# TopDrivers.net
KiCad netlist of a schematic drawn in Altium Designer
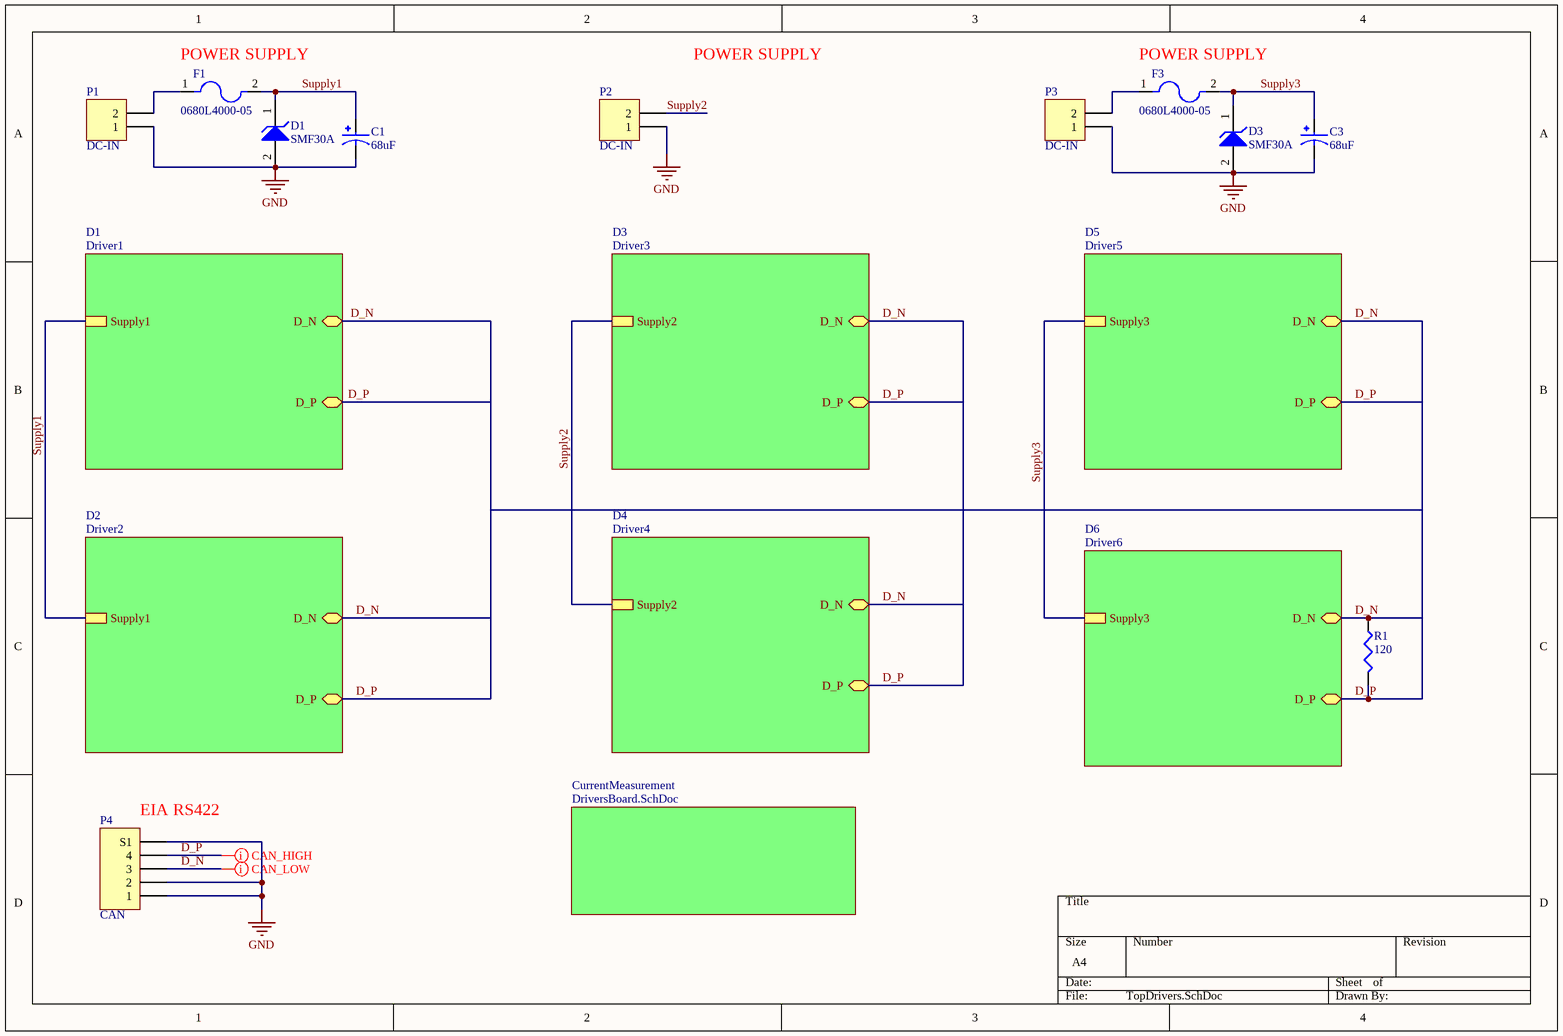
[diagram p0: TopDrivers.SchDoc]

(export (version "E")
  (design (tool "Eeschema 10.0.6"))
  (components
    (comp (ref "C1")
      (value "68uF")
      (footprint "CAP_50SVT68M")
      (fields (field (name "MP") "50SVT68M"))
      (libsource (lib "DriverLib") (part "50SVT68M"))
    )
    (comp (ref "C3")
      (value "68uF")
      (footprint "CAP_50SVT68M")
      (fields (field (name "MP") "50SVT68M"))
      (libsource (lib "DriverLib") (part "50SVT68M"))
    )
    (comp (ref "D1")
      (value "SMF30A")
      (footprint "ONSC-SOD-123FL-2-498_V")
      (description "200 W Transient Voltage Suppressor, 2-Pin SOD-123FL, Pb-Free, Tape and Reel")
      (fields (field (name "MANUFACTURER") "On Semiconductor") (field (name "PARTNUMBER") "SMF30AT1G"))
      (libsource (lib "SpaceBee") (part "SMF30AT1G"))
    )
    (comp (ref "D3")
      (value "SMF30A")
      (footprint "ONSC-SOD-123FL-2-498_V")
      (description "200 W Transient Voltage Suppressor, 2-Pin SOD-123FL, Pb-Free, Tape and Reel")
      (fields (field (name "MANUFACTURER") "On Semiconductor") (field (name "PARTNUMBER") "SMF30AT1G"))
      (libsource (lib "SpaceBee") (part "SMF30AT1G"))
    )
    (comp (ref "F1")
      (value "0680L4000-05")
      (footprint "FUSC6125X279N")
      (description "Surface mount bricks ¦ Silver Plated ¦ 2410 case size ¦ Slow Blow ¦ 4A ¦ Tape and Reel (5000 pcs.)")
      (fields (field (name "MF") "Bel Fuse"))
      (libsource (lib "DriverLib") (part "0680L4000-05"))
    )
    (comp (ref "F3")
      (value "0680L4000-05")
      (footprint "FUSC6125X279N")
      (description "Surface mount bricks ¦ Silver Plated ¦ 2410 case size ¦ Slow Blow ¦ 4A ¦ Tape and Reel (5000 pcs.)")
      (fields (field (name "MF") "Bel Fuse"))
      (libsource (lib "DriverLib") (part "0680L4000-05"))
    )
    (comp (ref "P1")
      (value "DC-IN")
      (footprint "MOLEX_1724480002")
      (description "Header, 2-Pin")
      (fields (field (name "PUBLISHER") "Altium Limited"))
      (libsource (lib "SpaceBee") (part "Header 2"))
    )
    (comp (ref "P2")
      (value "DC-IN")
      (footprint "MOLEX_1724480002")
      (description "Header, 2-Pin")
      (fields (field (name "PUBLISHER") "Altium Limited"))
      (libsource (lib "SpaceBee") (part "Header 2"))
    )
    (comp (ref "P3")
      (value "DC-IN")
      (footprint "MOLEX_1724480002")
      (description "Header, 2-Pin")
      (fields (field (name "PUBLISHER") "Altium Limited"))
      (libsource (lib "SpaceBee") (part "Header 2"))
    )
    (comp (ref "P4")
      (value "CAN")
      (footprint "MOLEX_5025850470")
      (description "Header, 5-Pin")
      (fields (field (name "PUBLISHER") "Altium Limited"))
      (libsource (lib "SpaceBee") (part "Header 5"))
    )
    (comp (ref "R1")
      (value "120")
      (footprint "J1-0603")
      (description "Resistor")
      (fields (field (name "Comment") "Res3") (field (name "PUBLISHER") "Altium Limited"))
      (libsource (lib "Miscellaneous Devices") (part "Res3"))
    )
  )
  (nets
    (net (code "1") (name "/D_N") (class "Default")
      (node (ref "P4") (pin "3") (pinfunction "3_3") (pintype "passive"))
      (node (ref "R1") (pin "1") (pinfunction "1_1") (pintype "passive"))
    )
    (net (code "2") (name "/D_P") (class "Default")
      (node (ref "P4") (pin "4") (pinfunction "4_4") (pintype "passive"))
      (node (ref "R1") (pin "2") (pinfunction "2_2") (pintype "passive"))
    )
    (net (code "3") (name "/Supply1") (class "Default")
      (node (ref "C1") (pin "1") (pinfunction "1_1") (pintype "passive"))
      (node (ref "D1") (pin "1") (pinfunction "K_1") (pintype "passive"))
      (node (ref "F1") (pin "2") (pinfunction "2_2") (pintype "passive"))
    )
    (net (code "4") (name "/Supply2") (class "Default")
      (node (ref "P2") (pin "2") (pinfunction "2_2") (pintype "passive"))
    )
    (net (code "5") (name "/Supply3") (class "Default")
      (node (ref "C3") (pin "1") (pinfunction "1_1") (pintype "passive"))
      (node (ref "D3") (pin "1") (pinfunction "K_1") (pintype "passive"))
      (node (ref "F3") (pin "2") (pinfunction "2_2") (pintype "passive"))
    )
    (net (code "6") (name "GND") (class "Default")
      (node (ref "C1") (pin "2") (pinfunction "2_2") (pintype "passive"))
      (node (ref "C3") (pin "2") (pinfunction "2_2") (pintype "passive"))
      (node (ref "D1") (pin "2") (pinfunction "A_2") (pintype "passive"))
      (node (ref "D3") (pin "2") (pinfunction "A_2") (pintype "passive"))
      (node (ref "P1") (pin "1") (pinfunction "1_1") (pintype "passive"))
      (node (ref "P2") (pin "1") (pinfunction "1_1") (pintype "passive"))
      (node (ref "P3") (pin "1") (pinfunction "1_1") (pintype "passive"))
      (node (ref "P4") (pin "1") (pinfunction "1_1") (pintype "passive"))
      (node (ref "P4") (pin "2") (pinfunction "2_2") (pintype "passive"))
      (node (ref "P4") (pin "S1") (pinfunction "S1_S1") (pintype "passive"))
    )
    (net (code "7") (name "Net-(F1-Pad1)") (class "Default")
      (node (ref "F1") (pin "1") (pinfunction "1_1") (pintype "passive"))
      (node (ref "P1") (pin "2") (pinfunction "2_2") (pintype "passive"))
    )
    (net (code "8") (name "Net-(F3-Pad1)") (class "Default")
      (node (ref "F3") (pin "1") (pinfunction "1_1") (pintype "passive"))
      (node (ref "P3") (pin "2") (pinfunction "2_2") (pintype "passive"))
    )
  )
)
